# RS232_to_CAN.net
KiCad netlist of a schematic drawn in EAGLE
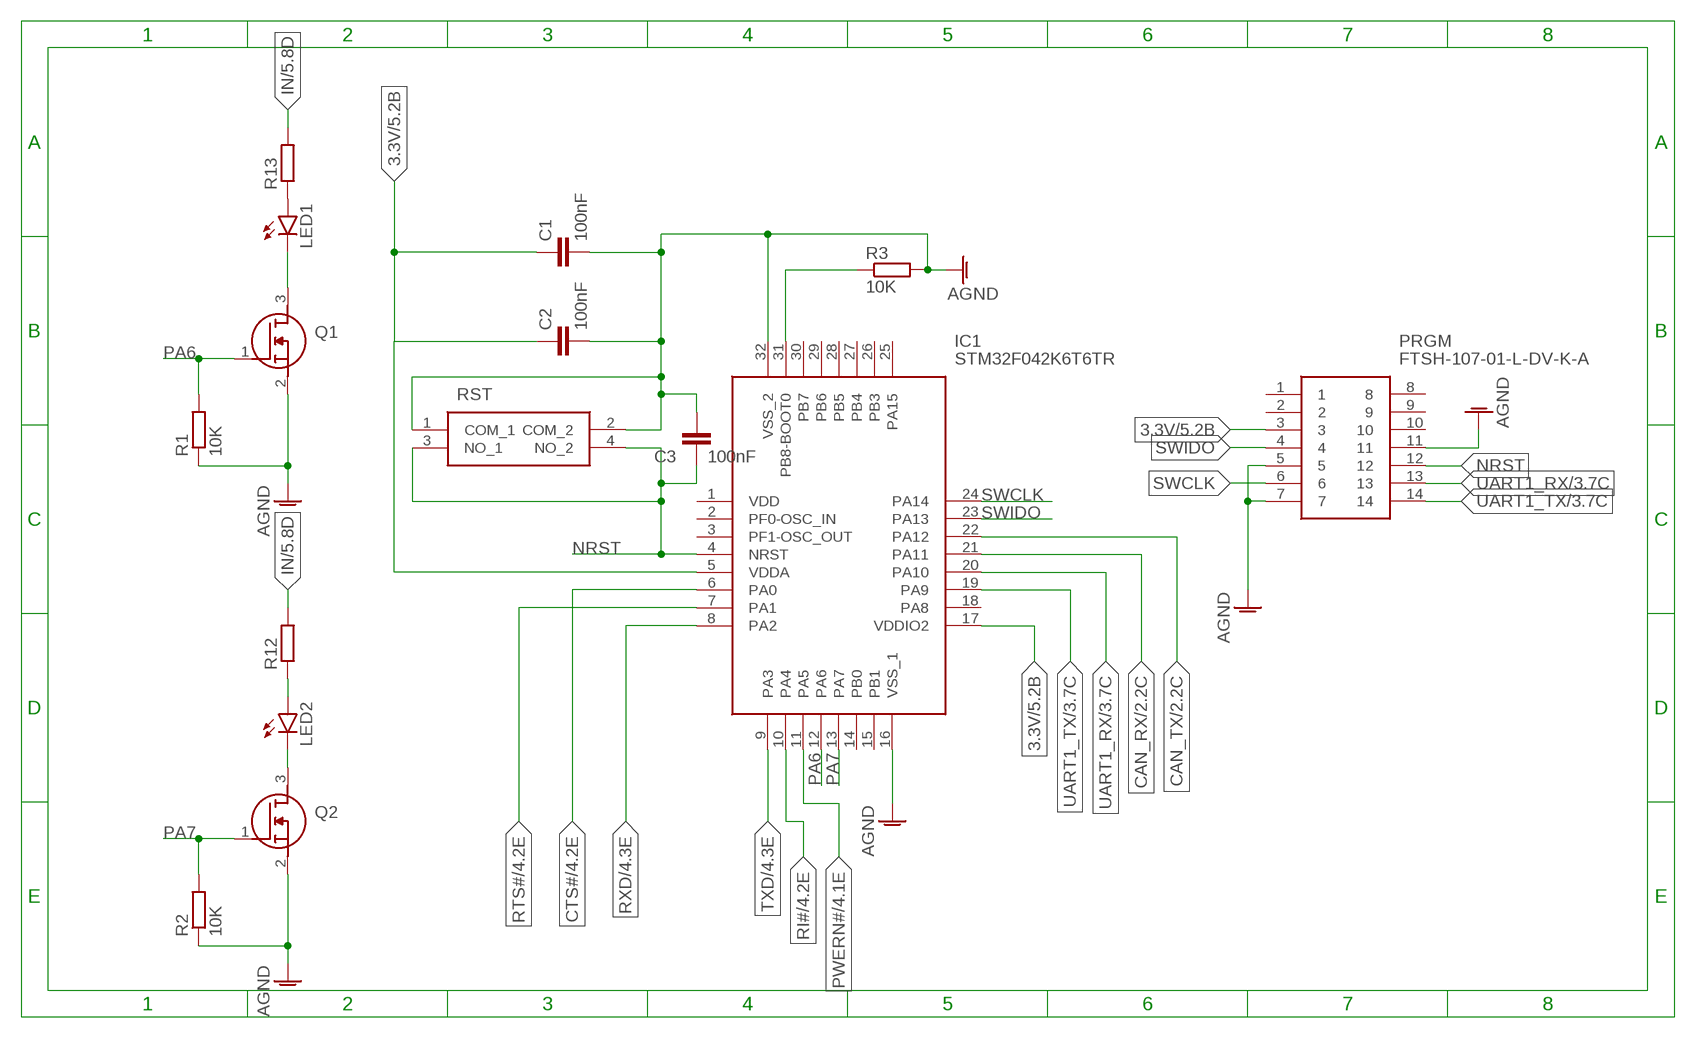
[diagram p0: schematic, sheet 1]
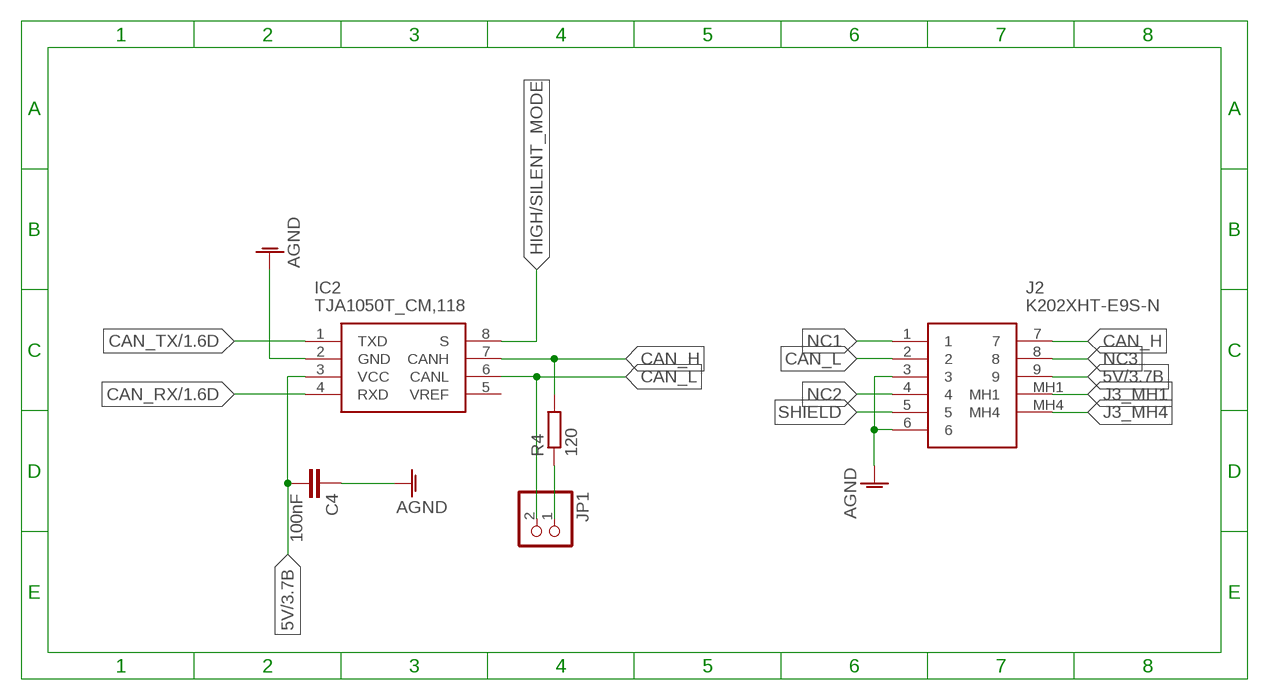
[diagram p1: schematic, sheet 2]
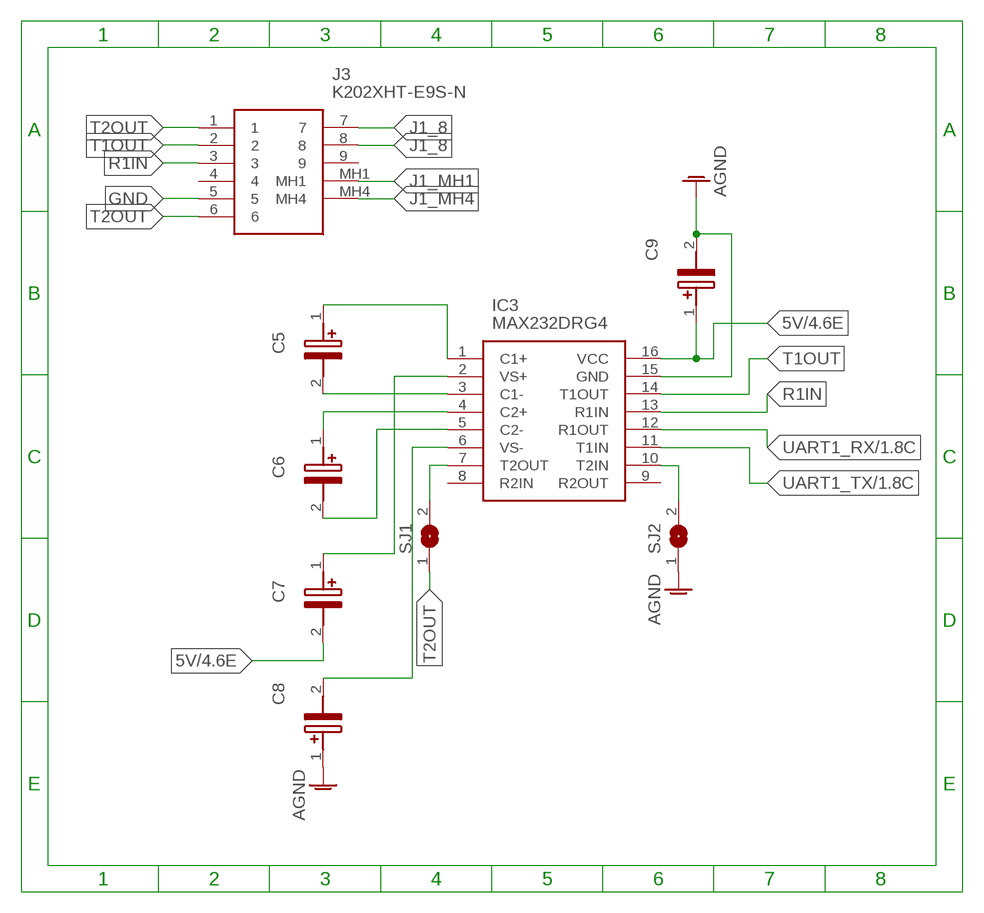
[diagram p2: schematic, sheet 3]
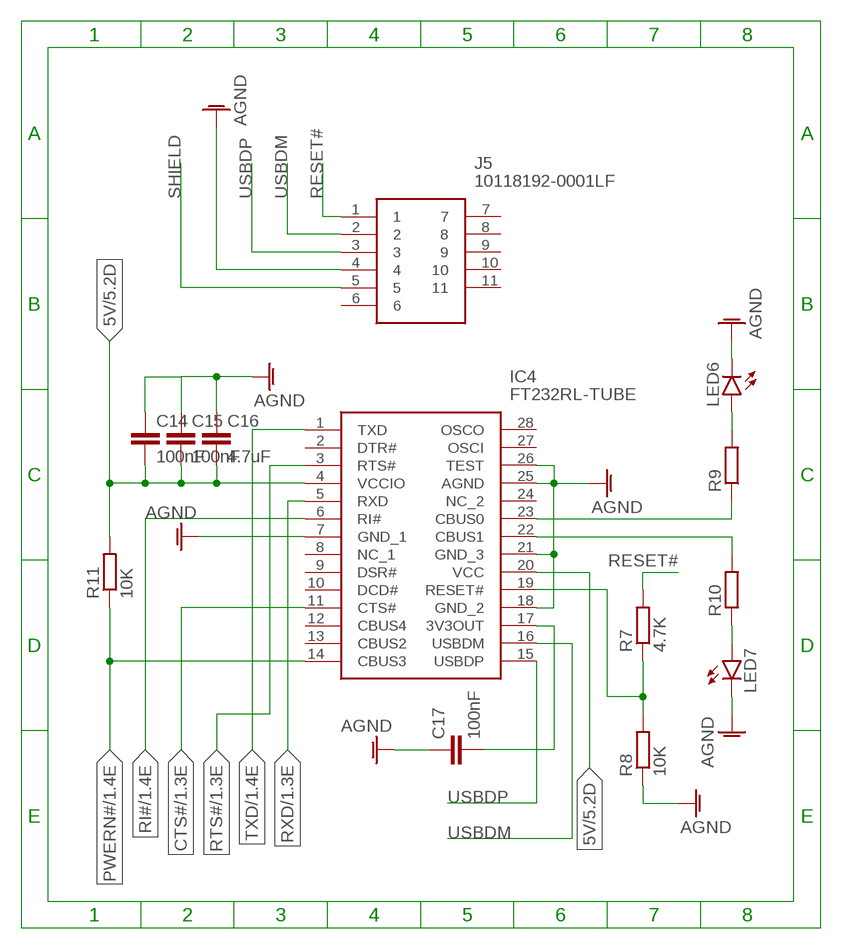
[diagram p3: schematic, sheet 4]
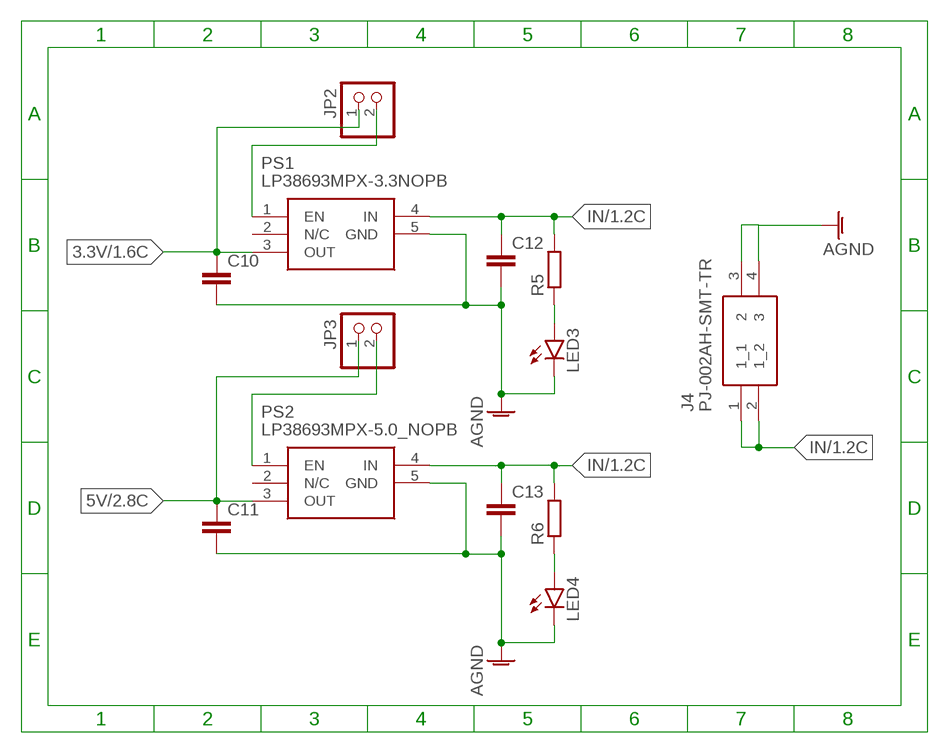
[diagram p4: schematic, sheet 5]

(export (version "E")
  (design (tool "Eeschema 10.0.6"))
  (components
    (comp (ref "C14")
      (value "100nF")
      (footprint "eagle-import:C1206")
      (libsource (lib "eagle-import") (part "C-EU_1206C1206"))
    )
    (comp (ref "C15")
      (value "100nF")
      (footprint "eagle-import:C1206")
      (libsource (lib "eagle-import") (part "C-EU_1206C1206"))
    )
    (comp (ref "C16")
      (value "4.7uF")
      (footprint "eagle-import:C1206")
      (libsource (lib "eagle-import") (part "C-EU_1206C1206"))
    )
    (comp (ref "C17")
      (value "100nF")
      (footprint "eagle-import:C1206")
      (libsource (lib "eagle-import") (part "C-EU_1206C1206"))
    )
    (comp (ref "IC4")
      (value "FT232RL-TUBE")
      (footprint "eagle-import:SOP65P780X200-28N")
      (fields (field (name "MOUSER_PART_NUMBER") "895-FT232RL-TUBE"))
      (libsource (lib "eagle-import") (part "FT232RL-TUBE"))
    )
    (comp (ref "J5")
      (value "10118192-0001LF")
      (footprint "eagle-import:101181920001LF")
      (fields (field (name "MOUSER_PART_NUMBER") "649-10118192-0001LF"))
      (libsource (lib "eagle-import") (part "10118192-0001LF"))
    )
    (comp (ref "LED6")
      (value "LED_1206SMT1206")
      (footprint "eagle-import:1206")
      (libsource (lib "eagle-import") (part "LED_1206SMT1206"))
    )
    (comp (ref "LED7")
      (value "LED_1206SMT1206")
      (footprint "eagle-import:1206")
      (libsource (lib "eagle-import") (part "LED_1206SMT1206"))
    )
    (comp (ref "R7")
      (value "4.7K")
      (footprint "eagle-import:R1206")
      (libsource (lib "eagle-import") (part "R-EU_1206R1206"))
    )
    (comp (ref "R8")
      (value "10K")
      (footprint "eagle-import:R1206")
      (libsource (lib "eagle-import") (part "R-EU_1206R1206"))
    )
    (comp (ref "R9")
      (value "R-EU_1206R1206")
      (footprint "eagle-import:R1206")
      (libsource (lib "eagle-import") (part "R-EU_1206R1206"))
    )
    (comp (ref "R10")
      (value "R-EU_1206R1206")
      (footprint "eagle-import:R1206")
      (libsource (lib "eagle-import") (part "R-EU_1206R1206"))
    )
    (comp (ref "R11")
      (value "10K")
      (footprint "eagle-import:R1206")
      (libsource (lib "eagle-import") (part "R-EU_1206R1206"))
    )
    (comp (ref "C5")
      (value "UWX1H010MCL2GB")
      (footprint "eagle-import:CAPAE430X550N")
      (fields (field (name "MOUSER_PART_NUMBER") "647-UWX1H010MCL2"))
      (libsource (lib "eagle-import") (part "UWX1H010MCL2GB"))
    )
    (comp (ref "C6")
      (value "UWX1H010MCL2GB")
      (footprint "eagle-import:CAPAE430X550N")
      (fields (field (name "MOUSER_PART_NUMBER") "647-UWX1H010MCL2"))
      (libsource (lib "eagle-import") (part "UWX1H010MCL2GB"))
    )
    (comp (ref "C7")
      (value "UWX1H010MCL2GB")
      (footprint "eagle-import:CAPAE430X550N")
      (fields (field (name "MOUSER_PART_NUMBER") "647-UWX1H010MCL2"))
      (libsource (lib "eagle-import") (part "UWX1H010MCL2GB"))
    )
    (comp (ref "C8")
      (value "UWX1H010MCL2GB")
      (footprint "eagle-import:CAPAE430X550N")
      (fields (field (name "MOUSER_PART_NUMBER") "647-UWX1H010MCL2"))
      (libsource (lib "eagle-import") (part "UWX1H010MCL2GB"))
    )
    (comp (ref "C9")
      (value "UWX1H010MCL2GB")
      (footprint "eagle-import:CAPAE430X550N")
      (fields (field (name "MOUSER_PART_NUMBER") "647-UWX1H010MCL2"))
      (libsource (lib "eagle-import") (part "UWX1H010MCL2GB"))
    )
    (comp (ref "IC3")
      (value "MAX232DRG4")
      (footprint "eagle-import:SOIC127P600X175-16N")
      (fields (field (name "MOUSER_PART_NUMBER") "595-MAX232DRG4"))
      (libsource (lib "eagle-import") (part "MAX232DRG4"))
    )
    (comp (ref "J3")
      (value "K202XHT-E9S-N")
      (footprint "eagle-import:K202XHTE9SN")
      (fields (field (name "MOUSER_PART_NUMBER") "806-K202XHT-E9S-N"))
      (libsource (lib "eagle-import") (part "K202XHT-E9S-N"))
    )
    (comp (ref "SJ1") (value "SJ") (footprint "eagle-import:SJ") (libsource (lib "eagle-import") (part "SJ")))
    (comp (ref "SJ2") (value "SJ") (footprint "eagle-import:SJ") (libsource (lib "eagle-import") (part "SJ")))
    (comp (ref "C4")
      (value "100nF")
      (footprint "eagle-import:C1206")
      (libsource (lib "eagle-import") (part "C-EU_1206C1206"))
    )
    (comp (ref "IC2")
      (value "TJA1050T_CM,118")
      (footprint "eagle-import:SOIC127P600X175-8N")
      (fields
        (field (name "MANUFACTURER_PART_NUMBER") "TJA1050T/CM,118")
        (field (name "MOUSER_PART_NUMBER") "771-TJA1050T/CM118")
      )
      (libsource (lib "eagle-import") (part "TJA1050T_CM,118"))
    )
    (comp (ref "J2")
      (value "K202XHT-E9S-N")
      (footprint "eagle-import:K202XHTE9SN")
      (fields (field (name "MOUSER_PART_NUMBER") "806-K202XHT-E9S-N"))
      (libsource (lib "eagle-import") (part "K202XHT-E9S-N"))
    )
    (comp (ref "JP1")
      (value "PINHEADER-1X2")
      (footprint "eagle-import:1X02")
      (libsource (lib "eagle-import") (part "PINHEADER-1X2"))
    )
    (comp (ref "R4")
      (value "120")
      (footprint "eagle-import:R1206")
      (libsource (lib "eagle-import") (part "R-EU_1206R1206"))
    )
    (comp (ref "C10")
      (value "C-EU_805C0805")
      (footprint "eagle-import:C0805")
      (libsource (lib "eagle-import") (part "C-EU_805C0805"))
    )
    (comp (ref "C11")
      (value "C-EU_805C0805")
      (footprint "eagle-import:C0805")
      (libsource (lib "eagle-import") (part "C-EU_805C0805"))
    )
    (comp (ref "C12")
      (value "C-EU_805C0805")
      (footprint "eagle-import:C0805")
      (libsource (lib "eagle-import") (part "C-EU_805C0805"))
    )
    (comp (ref "C13")
      (value "C-EU_805C0805")
      (footprint "eagle-import:C0805")
      (libsource (lib "eagle-import") (part "C-EU_805C0805"))
    )
    (comp (ref "J4")
      (value "PJ-002AH-SMT-TR")
      (footprint "eagle-import:PJ-002AH-SMT-TR")
      (fields (field (name "MOUSER_PART_NUMBER") "490-PJ-002AH-SMT-TR"))
      (libsource (lib "eagle-import") (part "PJ-002AH-SMT-TR"))
    )
    (comp (ref "JP2")
      (value "PINHEADER-1X2")
      (footprint "eagle-import:1X02")
      (libsource (lib "eagle-import") (part "PINHEADER-1X2"))
    )
    (comp (ref "JP3")
      (value "PINHEADER-1X2")
      (footprint "eagle-import:1X02")
      (libsource (lib "eagle-import") (part "PINHEADER-1X2"))
    )
    (comp (ref "LED3")
      (value "LED_1206SMT1206")
      (footprint "eagle-import:1206")
      (libsource (lib "eagle-import") (part "LED_1206SMT1206"))
    )
    (comp (ref "LED4")
      (value "LED_1206SMT1206")
      (footprint "eagle-import:1206")
      (libsource (lib "eagle-import") (part "LED_1206SMT1206"))
    )
    (comp (ref "PS1")
      (value "LP38693MPX-3.3NOPB")
      (footprint "eagle-import:SOT150P700X160-5N")
      (libsource (lib "eagle-import") (part "LP38693MPX-5.0_NOPB"))
    )
    (comp (ref "PS2")
      (value "LP38693MPX-5.0_NOPB")
      (footprint "eagle-import:SOT150P700X160-5N")
      (libsource (lib "eagle-import") (part "LP38693MPX-5.0_NOPB"))
    )
    (comp (ref "R5")
      (value "R-EU_1206R1206")
      (footprint "eagle-import:R1206")
      (libsource (lib "eagle-import") (part "R-EU_1206R1206"))
    )
    (comp (ref "R6")
      (value "R-EU_1206R1206")
      (footprint "eagle-import:R1206")
      (libsource (lib "eagle-import") (part "R-EU_1206R1206"))
    )
    (comp (ref "C1")
      (value "100nF")
      (footprint "eagle-import:C0805")
      (libsource (lib "eagle-import") (part "C-EU_805C0805"))
    )
    (comp (ref "C2")
      (value "100nF")
      (footprint "eagle-import:C0805")
      (libsource (lib "eagle-import") (part "C-EU_805C0805"))
    )
    (comp (ref "C3")
      (value "100nF")
      (footprint "eagle-import:C0805")
      (libsource (lib "eagle-import") (part "C-EU_805C0805"))
    )
    (comp (ref "IC1")
      (value "STM32F042K6T6TR")
      (footprint "eagle-import:QFP80P900X900X160-32N")
      (fields (field (name "MOUSER_PART_NUMBER") "511-STM32F042K6T6TR"))
      (libsource (lib "eagle-import") (part "STM32F042K6T6TR"))
    )
    (comp (ref "LED1")
      (value "LED_1206SMT1206")
      (footprint "eagle-import:1206")
      (libsource (lib "eagle-import") (part "LED_1206SMT1206"))
    )
    (comp (ref "LED2")
      (value "LED_1206SMT1206")
      (footprint "eagle-import:1206")
      (libsource (lib "eagle-import") (part "LED_1206SMT1206"))
    )
    (comp (ref "PRGM")
      (value "FTSH-107-01-L-DV-K-A")
      (footprint "eagle-import:FTSH10701LDVKA")
      (fields (field (name "MOUSER_PART_NUMBER") "200-FTSH10701LDVKA"))
      (libsource (lib "eagle-import") (part "FTSH-107-01-L-DV-K-A"))
    )
    (comp (ref "Q1")
      (value "FDN5632N-F085")
      (footprint "eagle-import:SOT95P237X122-3N")
      (fields (field (name "MOUSER_PART_NUMBER") "512-FDN5632N-F085"))
      (libsource (lib "eagle-import") (part "FDN5632N-F085"))
    )
    (comp (ref "Q2")
      (value "FDN5632N-F085")
      (footprint "eagle-import:SOT95P237X122-3N")
      (fields (field (name "MOUSER_PART_NUMBER") "512-FDN5632N-F085"))
      (libsource (lib "eagle-import") (part "FDN5632N-F085"))
    )
    (comp (ref "R1")
      (value "10K")
      (footprint "eagle-import:R0805")
      (libsource (lib "eagle-import") (part "R-EU_805R0805"))
    )
    (comp (ref "R2")
      (value "10K")
      (footprint "eagle-import:R0805")
      (libsource (lib "eagle-import") (part "R-EU_805R0805"))
    )
    (comp (ref "R3")
      (value "10K")
      (footprint "eagle-import:R1206")
      (libsource (lib "eagle-import") (part "R-EU_1206R1206"))
    )
    (comp (ref "R12")
      (value "R-EU_805R0805")
      (footprint "eagle-import:R0805")
      (libsource (lib "eagle-import") (part "R-EU_805R0805"))
    )
    (comp (ref "R13")
      (value "R-EU_805R0805")
      (footprint "eagle-import:R0805")
      (libsource (lib "eagle-import") (part "R-EU_805R0805"))
    )
    (comp (ref "RST")
      (value "PTS526_SM15_SMTR2_LFS")
      (footprint "eagle-import:PTS526SM15SMTR2LFS")
      (fields
        (field (name "MANUFACTURER_PART_NUMBER") "PTS526 SM15 SMTR2 LFS")
        (field (name "MOUSER_PART_NUMBER") "611-PTS526SM15SMTR2L")
      )
      (libsource (lib "eagle-import") (part "PTS526_SM15_SMTR2_LFS"))
    )
  )
  (nets
    (net (code "1") (name "3.3V") (class "Default")
      (node (ref "C1") (pin "1") (pinfunction "1_1") (pintype "passive"))
      (node (ref "C10") (pin "1") (pinfunction "1_1") (pintype "passive"))
      (node (ref "C2") (pin "1") (pinfunction "1_1") (pintype "passive"))
      (node (ref "IC1") (pin "17") (pinfunction "VDDIO2_17") (pintype "bidirectional"))
      (node (ref "IC1") (pin "5") (pinfunction "VDDA_5") (pintype "bidirectional"))
      (node (ref "JP2") (pin "1") (pinfunction "1_1") (pintype "passive"))
      (node (ref "PRGM") (pin "3") (pinfunction "3_3") (pintype "bidirectional"))
      (node (ref "PS1") (pin "3") (pinfunction "OUT_3") (pintype "bidirectional"))
    )
    (net (code "2") (name "5V") (class "Default")
      (node (ref "C11") (pin "1") (pinfunction "1_1") (pintype "passive"))
      (node (ref "C14") (pin "2") (pinfunction "2_2") (pintype "passive"))
      (node (ref "C15") (pin "2") (pinfunction "2_2") (pintype "passive"))
      (node (ref "C16") (pin "2") (pinfunction "2_2") (pintype "passive"))
      (node (ref "C4") (pin "2") (pinfunction "2_2") (pintype "passive"))
      (node (ref "C7") (pin "2") (pinfunction "-_2") (pintype "bidirectional"))
      (node (ref "C9") (pin "1") (pinfunction "+_1") (pintype "bidirectional"))
      (node (ref "IC2") (pin "3") (pinfunction "VCC_3") (pintype "bidirectional"))
      (node (ref "IC3") (pin "16") (pinfunction "VCC_16") (pintype "bidirectional"))
      (node (ref "IC4") (pin "20") (pinfunction "VCC_20") (pintype "bidirectional"))
      (node (ref "IC4") (pin "4") (pinfunction "VCCIO_4") (pintype "bidirectional"))
      (node (ref "J2") (pin "9") (pinfunction "9_9") (pintype "bidirectional"))
      (node (ref "JP3") (pin "1") (pinfunction "1_1") (pintype "passive"))
      (node (ref "PS2") (pin "3") (pinfunction "OUT_3") (pintype "bidirectional"))
      (node (ref "R11") (pin "2") (pinfunction "2_2") (pintype "passive"))
    )
    (net (code "3") (name "AGND") (class "Default")
      (node (ref "C1") (pin "2") (pinfunction "2_2") (pintype "passive"))
      (node (ref "C10") (pin "2") (pinfunction "2_2") (pintype "passive"))
      (node (ref "C11") (pin "2") (pinfunction "2_2") (pintype "passive"))
      (node (ref "C12") (pin "2") (pinfunction "2_2") (pintype "passive"))
      (node (ref "C13") (pin "2") (pinfunction "2_2") (pintype "passive"))
      (node (ref "C14") (pin "1") (pinfunction "1_1") (pintype "passive"))
      (node (ref "C15") (pin "1") (pinfunction "1_1") (pintype "passive"))
      (node (ref "C16") (pin "1") (pinfunction "1_1") (pintype "passive"))
      (node (ref "C17") (pin "1") (pinfunction "1_1") (pintype "passive"))
      (node (ref "C2") (pin "2") (pinfunction "2_2") (pintype "passive"))
      (node (ref "C3") (pin "1") (pinfunction "1_1") (pintype "passive"))
      (node (ref "C4") (pin "1") (pinfunction "1_1") (pintype "passive"))
      (node (ref "C8") (pin "1") (pinfunction "+_1") (pintype "bidirectional"))
      (node (ref "C9") (pin "2") (pinfunction "-_2") (pintype "bidirectional"))
      (node (ref "IC1") (pin "16") (pinfunction "VSS_1_16") (pintype "bidirectional"))
      (node (ref "IC1") (pin "32") (pinfunction "VSS_2_32") (pintype "bidirectional"))
      (node (ref "IC2") (pin "2") (pinfunction "GND_2") (pintype "bidirectional"))
      (node (ref "IC3") (pin "15") (pinfunction "GND_15") (pintype "bidirectional"))
      (node (ref "IC4") (pin "18") (pinfunction "GND_2_18") (pintype "bidirectional"))
      (node (ref "IC4") (pin "21") (pinfunction "GND_3_21") (pintype "bidirectional"))
      (node (ref "IC4") (pin "25") (pinfunction "AGND_25") (pintype "bidirectional"))
      (node (ref "IC4") (pin "26") (pinfunction "TEST_26") (pintype "bidirectional"))
      (node (ref "IC4") (pin "7") (pinfunction "GND_1_7") (pintype "bidirectional"))
      (node (ref "J2") (pin "3") (pinfunction "3_3") (pintype "bidirectional"))
      (node (ref "J2") (pin "6") (pinfunction "6_6") (pintype "bidirectional"))
      (node (ref "J4") (pin "3") (pinfunction "2_3") (pintype "bidirectional"))
      (node (ref "J4") (pin "4") (pinfunction "3_4") (pintype "bidirectional"))
      (node (ref "J5") (pin "4") (pinfunction "4_4") (pintype "bidirectional"))
      (node (ref "LED3") (pin "C") (pinfunction "C_C") (pintype "passive"))
      (node (ref "LED4") (pin "C") (pinfunction "C_C") (pintype "passive"))
      (node (ref "LED6") (pin "C") (pinfunction "C_C") (pintype "passive"))
      (node (ref "LED7") (pin "C") (pinfunction "C_C") (pintype "passive"))
      (node (ref "PRGM") (pin "11") (pinfunction "11_11") (pintype "bidirectional"))
      (node (ref "PRGM") (pin "5") (pinfunction "5_5") (pintype "bidirectional"))
      (node (ref "PRGM") (pin "7") (pinfunction "7_7") (pintype "bidirectional"))
      (node (ref "PS1") (pin "5") (pinfunction "GND_5") (pintype "bidirectional"))
      (node (ref "PS2") (pin "5") (pinfunction "GND_5") (pintype "bidirectional"))
      (node (ref "Q1") (pin "2") (pinfunction "S_2") (pintype "bidirectional"))
      (node (ref "Q2") (pin "2") (pinfunction "S_2") (pintype "bidirectional"))
      (node (ref "R1") (pin "1") (pinfunction "1_1") (pintype "passive"))
      (node (ref "R2") (pin "1") (pinfunction "1_1") (pintype "passive"))
      (node (ref "R3") (pin "2") (pinfunction "2_2") (pintype "passive"))
      (node (ref "R8") (pin "1") (pinfunction "1_1") (pintype "passive"))
      (node (ref "RST") (pin "1") (pinfunction "COM_1_1") (pintype "bidirectional"))
      (node (ref "RST") (pin "2") (pinfunction "COM_2_2") (pintype "bidirectional"))
      (node (ref "SJ2") (pin "1") (pinfunction "1_1") (pintype "passive"))
    )
    (net (code "4") (name "CAN_H") (class "Default")
      (node (ref "IC2") (pin "7") (pinfunction "CANH_7") (pintype "bidirectional"))
      (node (ref "J2") (pin "7") (pinfunction "7_7") (pintype "bidirectional"))
      (node (ref "R4") (pin "2") (pinfunction "2_2") (pintype "passive"))
    )
    (net (code "5") (name "CAN_L") (class "Default")
      (node (ref "IC2") (pin "6") (pinfunction "CANL_6") (pintype "bidirectional"))
      (node (ref "J2") (pin "2") (pinfunction "2_2") (pintype "bidirectional"))
      (node (ref "JP1") (pin "2") (pinfunction "2_2") (pintype "passive"))
    )
    (net (code "6") (name "CAN_RX") (class "Default")
      (node (ref "IC1") (pin "21") (pinfunction "PA11_21") (pintype "bidirectional"))
      (node (ref "IC2") (pin "4") (pinfunction "RXD_4") (pintype "bidirectional"))
    )
    (net (code "7") (name "CAN_TX") (class "Default")
      (node (ref "IC1") (pin "22") (pinfunction "PA12_22") (pintype "bidirectional"))
      (node (ref "IC2") (pin "1") (pinfunction "TXD_1") (pintype "bidirectional"))
    )
    (net (code "8") (name "CTS#") (class "Default")
      (node (ref "IC1") (pin "6") (pinfunction "PA0_6") (pintype "bidirectional"))
      (node (ref "IC4") (pin "11") (pinfunction "CTS#_11") (pintype "bidirectional"))
    )
    (net (code "9") (name "GND") (class "Default")
      (node (ref "J3") (pin "5") (pinfunction "5_5") (pintype "bidirectional"))
    )
    (net (code "10") (name "HIGH{slash}SILENT_MODE") (class "Default")
      (node (ref "IC2") (pin "8") (pinfunction "S_8") (pintype "bidirectional"))
    )
    (net (code "11") (name "IN") (class "Default")
      (node (ref "C12") (pin "1") (pinfunction "1_1") (pintype "passive"))
      (node (ref "C13") (pin "1") (pinfunction "1_1") (pintype "passive"))
      (node (ref "J4") (pin "1") (pinfunction "1_1_1") (pintype "bidirectional"))
      (node (ref "J4") (pin "2") (pinfunction "1_2_2") (pintype "bidirectional"))
      (node (ref "LED1") (pin "C") (pinfunction "C_C") (pintype "passive"))
      (node (ref "LED2") (pin "C") (pinfunction "C_C") (pintype "passive"))
      (node (ref "PS1") (pin "4") (pinfunction "IN_4") (pintype "bidirectional"))
      (node (ref "PS2") (pin "4") (pinfunction "IN_4") (pintype "bidirectional"))
      (node (ref "Q1") (pin "3") (pinfunction "D_3") (pintype "bidirectional"))
      (node (ref "Q2") (pin "3") (pinfunction "D_3") (pintype "bidirectional"))
      (node (ref "R5") (pin "2") (pinfunction "2_2") (pintype "passive"))
      (node (ref "R6") (pin "2") (pinfunction "2_2") (pintype "passive"))
    )
    (net (code "12") (name "J1_8") (class "Default")
      (node (ref "J3") (pin "7") (pinfunction "7_7") (pintype "bidirectional"))
      (node (ref "J3") (pin "8") (pinfunction "8_8") (pintype "bidirectional"))
    )
    (net (code "13") (name "J1_MH1") (class "Default")
      (node (ref "J3") (pin "MH1") (pinfunction "MH1_MH1") (pintype "bidirectional"))
    )
    (net (code "14") (name "J1_MH4") (class "Default")
      (node (ref "J3") (pin "MH4") (pinfunction "MH4_MH4") (pintype "bidirectional"))
    )
    (net (code "15") (name "J3_MH1") (class "Default")
      (node (ref "J2") (pin "MH1") (pinfunction "MH1_MH1") (pintype "bidirectional"))
    )
    (net (code "16") (name "J3_MH4") (class "Default")
      (node (ref "J2") (pin "MH4") (pinfunction "MH4_MH4") (pintype "bidirectional"))
    )
    (net (code "17") (name "NC1") (class "Default")
      (node (ref "J2") (pin "1") (pinfunction "1_1") (pintype "bidirectional"))
    )
    (net (code "18") (name "NC2") (class "Default")
      (node (ref "J2") (pin "4") (pinfunction "4_4") (pintype "bidirectional"))
    )
    (net (code "19") (name "NC3") (class "Default")
      (node (ref "J2") (pin "8") (pinfunction "8_8") (pintype "bidirectional"))
    )
    (net (code "20") (name "NRST") (class "Default")
      (node (ref "C3") (pin "2") (pinfunction "2_2") (pintype "passive"))
      (node (ref "IC1") (pin "4") (pinfunction "NRST_4") (pintype "bidirectional"))
      (node (ref "PRGM") (pin "12") (pinfunction "12_12") (pintype "bidirectional"))
      (node (ref "RST") (pin "3") (pinfunction "NO_1_3") (pintype "bidirectional"))
      (node (ref "RST") (pin "4") (pinfunction "NO_2_4") (pintype "bidirectional"))
    )
    (net (code "21") (name "Net-(C5-+)") (class "Default")
      (node (ref "C5") (pin "1") (pinfunction "+_1") (pintype "bidirectional"))
      (node (ref "IC3") (pin "1") (pinfunction "C1+_1") (pintype "bidirectional"))
    )
    (net (code "22") (name "Net-(C5--)") (class "Default")
      (node (ref "C5") (pin "2") (pinfunction "-_2") (pintype "bidirectional"))
      (node (ref "IC3") (pin "3") (pinfunction "C1-_3") (pintype "bidirectional"))
    )
    (net (code "23") (name "Net-(C6-+)") (class "Default")
      (node (ref "C6") (pin "1") (pinfunction "+_1") (pintype "bidirectional"))
      (node (ref "IC3") (pin "4") (pinfunction "C2+_4") (pintype "bidirectional"))
    )
    (net (code "24") (name "Net-(C6--)") (class "Default")
      (node (ref "C6") (pin "2") (pinfunction "-_2") (pintype "bidirectional"))
      (node (ref "IC3") (pin "5") (pinfunction "C2-_5") (pintype "bidirectional"))
    )
    (net (code "25") (name "Net-(C7-+)") (class "Default")
      (node (ref "C7") (pin "1") (pinfunction "+_1") (pintype "bidirectional"))
      (node (ref "IC3") (pin "2") (pinfunction "VS+_2") (pintype "bidirectional"))
    )
    (net (code "26") (name "Net-(C8--)") (class "Default")
      (node (ref "C8") (pin "2") (pinfunction "-_2") (pintype "bidirectional"))
      (node (ref "IC3") (pin "6") (pinfunction "VS-_6") (pintype "bidirectional"))
    )
    (net (code "27") (name "Net-(IC1-PB8-BOOT0)") (class "Default")
      (node (ref "IC1") (pin "31") (pinfunction "PB8-BOOT0_31") (pintype "bidirectional"))
      (node (ref "R3") (pin "1") (pinfunction "1_1") (pintype "passive"))
    )
    (net (code "28") (name "Net-(IC3-T2IN)") (class "Default")
      (node (ref "IC3") (pin "10") (pinfunction "T2IN_10") (pintype "bidirectional"))
      (node (ref "SJ2") (pin "2") (pinfunction "2_2") (pintype "passive"))
    )
    (net (code "29") (name "Net-(IC4-3V3OUT)") (class "Default")
      (node (ref "C17") (pin "2") (pinfunction "2_2") (pintype "passive"))
      (node (ref "IC4") (pin "17") (pinfunction "3V3OUT_17") (pintype "bidirectional"))
    )
    (net (code "30") (name "Net-(IC4-CBUS0)") (class "Default")
      (node (ref "IC4") (pin "23") (pinfunction "CBUS0_23") (pintype "bidirectional"))
      (node (ref "R9") (pin "1") (pinfunction "1_1") (pintype "passive"))
    )
    (net (code "31") (name "Net-(IC4-CBUS1)") (class "Default")
      (node (ref "IC4") (pin "22") (pinfunction "CBUS1_22") (pintype "bidirectional"))
      (node (ref "R10") (pin "2") (pinfunction "2_2") (pintype "passive"))
    )
    (net (code "32") (name "Net-(IC4-RESET#)") (class "Default")
      (node (ref "IC4") (pin "19") (pinfunction "RESET#_19") (pintype "bidirectional"))
      (node (ref "R7") (pin "1") (pinfunction "1_1") (pintype "passive"))
      (node (ref "R8") (pin "2") (pinfunction "2_2") (pintype "passive"))
    )
    (net (code "33") (name "Net-(JP1-Pad1)") (class "Default")
      (node (ref "JP1") (pin "1") (pinfunction "1_1") (pintype "passive"))
      (node (ref "R4") (pin "1") (pinfunction "1_1") (pintype "passive"))
    )
    (net (code "34") (name "Net-(LED1-PadA)") (class "Default")
      (node (ref "LED1") (pin "A") (pinfunction "A_A") (pintype "passive"))
      (node (ref "R13") (pin "1") (pinfunction "1_1") (pintype "passive"))
    )
    (net (code "35") (name "Net-(LED2-PadA)") (class "Default")
      (node (ref "LED2") (pin "A") (pinfunction "A_A") (pintype "passive"))
      (node (ref "R12") (pin "1") (pinfunction "1_1") (pintype "passive"))
    )
    (net (code "36") (name "Net-(LED3-PadA)") (class "Default")
      (node (ref "LED3") (pin "A") (pinfunction "A_A") (pintype "passive"))
      (node (ref "R5") (pin "1") (pinfunction "1_1") (pintype "passive"))
    )
    (net (code "37") (name "Net-(LED4-PadA)") (class "Default")
      (node (ref "LED4") (pin "A") (pinfunction "A_A") (pintype "passive"))
      (node (ref "R6") (pin "1") (pinfunction "1_1") (pintype "passive"))
    )
    (net (code "38") (name "Net-(LED6-PadA)") (class "Default")
      (node (ref "LED6") (pin "A") (pinfunction "A_A") (pintype "passive"))
      (node (ref "R9") (pin "2") (pinfunction "2_2") (pintype "passive"))
    )
    (net (code "39") (name "Net-(LED7-PadA)") (class "Default")
      (node (ref "LED7") (pin "A") (pinfunction "A_A") (pintype "passive"))
      (node (ref "R10") (pin "1") (pinfunction "1_1") (pintype "passive"))
    )
    (net (code "40") (name "Net-(PS1-EN)") (class "Default")
      (node (ref "JP2") (pin "2") (pinfunction "2_2") (pintype "passive"))
      (node (ref "PS1") (pin "1") (pinfunction "EN_1") (pintype "bidirectional"))
    )
    (net (code "41") (name "Net-(PS2-EN)") (class "Default")
      (node (ref "JP3") (pin "2") (pinfunction "2_2") (pintype "passive"))
      (node (ref "PS2") (pin "1") (pinfunction "EN_1") (pintype "bidirectional"))
    )
    (net (code "42") (name "PA6") (class "Default")
      (node (ref "IC1") (pin "12") (pinfunction "PA6_12") (pintype "bidirectional"))
      (node (ref "Q1") (pin "1") (pinfunction "G_1") (pintype "bidirectional"))
      (node (ref "R1") (pin "2") (pinfunction "2_2") (pintype "passive"))
    )
    (net (code "43") (name "PA7") (class "Default")
      (node (ref "IC1") (pin "13") (pinfunction "PA7_13") (pintype "bidirectional"))
      (node (ref "Q2") (pin "1") (pinfunction "G_1") (pintype "bidirectional"))
      (node (ref "R2") (pin "2") (pinfunction "2_2") (pintype "passive"))
    )
    (net (code "44") (name "PWERN#") (class "Default")
      (node (ref "IC1") (pin "11") (pinfunction "PA5_11") (pintype "bidirectional"))
      (node (ref "IC4") (pin "14") (pinfunction "CBUS3_14") (pintype "bidirectional"))
      (node (ref "R11") (pin "1") (pinfunction "1_1") (pintype "passive"))
    )
    (net (code "45") (name "R1IN") (class "Default")
      (node (ref "IC3") (pin "13") (pinfunction "R1IN_13") (pintype "bidirectional"))
      (node (ref "J3") (pin "3") (pinfunction "3_3") (pintype "bidirectional"))
    )
    (net (code "46") (name "RESET#") (class "Default")
      (node (ref "J5") (pin "1") (pinfunction "1_1") (pintype "bidirectional"))
      (node (ref "R7") (pin "2") (pinfunction "2_2") (pintype "passive"))
    )
    (net (code "47") (name "RI#") (class "Default")
      (node (ref "IC1") (pin "10") (pinfunction "PA4_10") (pintype "bidirectional"))
      (node (ref "IC4") (pin "6") (pinfunction "RI#_6") (pintype "bidirectional"))
    )
    (net (code "48") (name "RTS#") (class "Default")
      (node (ref "IC1") (pin "7") (pinfunction "PA1_7") (pintype "bidirectional"))
      (node (ref "IC4") (pin "3") (pinfunction "RTS#_3") (pintype "bidirectional"))
    )
    (net (code "49") (name "RXD") (class "Default")
      (node (ref "IC1") (pin "8") (pinfunction "PA2_8") (pintype "bidirectional"))
      (node (ref "IC4") (pin "5") (pinfunction "RXD_5") (pintype "bidirectional"))
    )
    (net (code "50") (name "SHIELD") (class "Default")
      (node (ref "J2") (pin "5") (pinfunction "5_5") (pintype "bidirectional"))
      (node (ref "J5") (pin "5") (pinfunction "5_5") (pintype "bidirectional"))
    )
    (net (code "51") (name "SWCLK") (class "Default")
      (node (ref "IC1") (pin "24") (pinfunction "PA14_24") (pintype "bidirectional"))
      (node (ref "PRGM") (pin "6") (pinfunction "6_6") (pintype "bidirectional"))
    )
    (net (code "52") (name "SWIDO") (class "Default")
      (node (ref "IC1") (pin "23") (pinfunction "PA13_23") (pintype "bidirectional"))
      (node (ref "PRGM") (pin "4") (pinfunction "4_4") (pintype "bidirectional"))
    )
    (net (code "53") (name "T1OUT") (class "Default")
      (node (ref "IC3") (pin "14") (pinfunction "T1OUT_14") (pintype "bidirectional"))
      (node (ref "J3") (pin "2") (pinfunction "2_2") (pintype "bidirectional"))
    )
    (net (code "54") (name "T2OUT") (class "Default")
      (node (ref "IC3") (pin "7") (pinfunction "T2OUT_7") (pintype "bidirectional"))
      (node (ref "J3") (pin "1") (pinfunction "1_1") (pintype "bidirectional"))
      (node (ref "J3") (pin "6") (pinfunction "6_6") (pintype "bidirectional"))
      (node (ref "SJ1") (pin "1") (pinfunction "1_1") (pintype "passive"))
      (node (ref "SJ1") (pin "2") (pinfunction "2_2") (pintype "passive"))
    )
    (net (code "55") (name "TXD") (class "Default")
      (node (ref "IC1") (pin "9") (pinfunction "PA3_9") (pintype "bidirectional"))
      (node (ref "IC4") (pin "1") (pinfunction "TXD_1") (pintype "bidirectional"))
    )
    (net (code "56") (name "UART1_RX") (class "Default")
      (node (ref "IC1") (pin "20") (pinfunction "PA10_20") (pintype "bidirectional"))
      (node (ref "IC3") (pin "12") (pinfunction "R1OUT_12") (pintype "bidirectional"))
      (node (ref "PRGM") (pin "13") (pinfunction "13_13") (pintype "bidirectional"))
    )
    (net (code "57") (name "UART1_TX") (class "Default")
      (node (ref "IC1") (pin "19") (pinfunction "PA9_19") (pintype "bidirectional"))
      (node (ref "IC3") (pin "11") (pinfunction "T1IN_11") (pintype "bidirectional"))
      (node (ref "PRGM") (pin "14") (pinfunction "14_14") (pintype "bidirectional"))
    )
    (net (code "58") (name "USBDM") (class "Default")
      (node (ref "IC4") (pin "16") (pinfunction "USBDM_16") (pintype "bidirectional"))
      (node (ref "J5") (pin "2") (pinfunction "2_2") (pintype "bidirectional"))
    )
    (net (code "59") (name "USBDP") (class "Default")
      (node (ref "IC4") (pin "15") (pinfunction "USBDP_15") (pintype "bidirectional"))
      (node (ref "J5") (pin "3") (pinfunction "3_3") (pintype "bidirectional"))
    )
    (net (code "60") (name "unconnected-(IC1-PA8-Pad18)") (class "Default")
      (node (ref "IC1") (pin "18") (pinfunction "PA8_18") (pintype "bidirectional"))
    )
    (net (code "61") (name "unconnected-(IC1-PA15-Pad25)") (class "Default")
      (node (ref "IC1") (pin "25") (pinfunction "PA15_25") (pintype "bidirectional"))
    )
    (net (code "62") (name "unconnected-(IC1-PB0-Pad14)") (class "Default")
      (node (ref "IC1") (pin "14") (pinfunction "PB0_14") (pintype "bidirectional"))
    )
    (net (code "63") (name "unconnected-(IC1-PB1-Pad15)") (class "Default")
      (node (ref "IC1") (pin "15") (pinfunction "PB1_15") (pintype "bidirectional"))
    )
    (net (code "64") (name "unconnected-(IC1-PB3-Pad26)") (class "Default")
      (node (ref "IC1") (pin "26") (pinfunction "PB3_26") (pintype "bidirectional"))
    )
    (net (code "65") (name "unconnected-(IC1-PB4-Pad27)") (class "Default")
      (node (ref "IC1") (pin "27") (pinfunction "PB4_27") (pintype "bidirectional"))
    )
    (net (code "66") (name "unconnected-(IC1-PB5-Pad28)") (class "Default")
      (node (ref "IC1") (pin "28") (pinfunction "PB5_28") (pintype "bidirectional"))
    )
    (net (code "67") (name "unconnected-(IC1-PB6-Pad29)") (class "Default")
      (node (ref "IC1") (pin "29") (pinfunction "PB6_29") (pintype "bidirectional"))
    )
    (net (code "68") (name "unconnected-(IC1-PB7-Pad30)") (class "Default")
      (node (ref "IC1") (pin "30") (pinfunction "PB7_30") (pintype "bidirectional"))
    )
    (net (code "69") (name "unconnected-(IC1-PF0-OSC_IN-Pad2)") (class "Default")
      (node (ref "IC1") (pin "2") (pinfunction "PF0-OSC_IN_2") (pintype "bidirectional"))
    )
    (net (code "70") (name "unconnected-(IC1-PF1-OSC_OUT-Pad3)") (class "Default")
      (node (ref "IC1") (pin "3") (pinfunction "PF1-OSC_OUT_3") (pintype "bidirectional"))
    )
    (net (code "71") (name "unconnected-(IC1-VDD-Pad1)") (class "Default")
      (node (ref "IC1") (pin "1") (pinfunction "VDD_1") (pintype "bidirectional"))
    )
    (net (code "72") (name "unconnected-(IC2-VREF-Pad5)") (class "Default")
      (node (ref "IC2") (pin "5") (pinfunction "VREF_5") (pintype "bidirectional"))
    )
    (net (code "73") (name "unconnected-(IC3-R2IN-Pad8)") (class "Default")
      (node (ref "IC3") (pin "8") (pinfunction "R2IN_8") (pintype "bidirectional"))
    )
    (net (code "74") (name "unconnected-(IC3-R2OUT-Pad9)") (class "Default")
      (node (ref "IC3") (pin "9") (pinfunction "R2OUT_9") (pintype "bidirectional"))
    )
    (net (code "75") (name "unconnected-(IC4-CBUS2-Pad13)") (class "Default")
      (node (ref "IC4") (pin "13") (pinfunction "CBUS2_13") (pintype "bidirectional"))
    )
    (net (code "76") (name "unconnected-(IC4-CBUS4-Pad12)") (class "Default")
      (node (ref "IC4") (pin "12") (pinfunction "CBUS4_12") (pintype "bidirectional"))
    )
    (net (code "77") (name "unconnected-(IC4-DCD#-Pad10)") (class "Default")
      (node (ref "IC4") (pin "10") (pinfunction "DCD#_10") (pintype "bidirectional"))
    )
    (net (code "78") (name "unconnected-(IC4-DSR#-Pad9)") (class "Default")
      (node (ref "IC4") (pin "9") (pinfunction "DSR#_9") (pintype "bidirectional"))
    )
    (net (code "79") (name "unconnected-(IC4-DTR#-Pad2)") (class "Default")
      (node (ref "IC4") (pin "2") (pinfunction "DTR#_2") (pintype "bidirectional"))
    )
    (net (code "80") (name "unconnected-(IC4-NC_1-Pad8)") (class "Default")
      (node (ref "IC4") (pin "8") (pinfunction "NC_1_8") (pintype "bidirectional"))
    )
    (net (code "81") (name "unconnected-(IC4-NC_2-Pad24)") (class "Default")
      (node (ref "IC4") (pin "24") (pinfunction "NC_2_24") (pintype "bidirectional"))
    )
    (net (code "82") (name "unconnected-(IC4-OSCI-Pad27)") (class "Default")
      (node (ref "IC4") (pin "27") (pinfunction "OSCI_27") (pintype "bidirectional"))
    )
    (net (code "83") (name "unconnected-(IC4-OSCO-Pad28)") (class "Default")
      (node (ref "IC4") (pin "28") (pinfunction "OSCO_28") (pintype "bidirectional"))
    )
    (net (code "84") (name "unconnected-(J3-Pad4)") (class "Default")
      (node (ref "J3") (pin "4") (pinfunction "4_4") (pintype "bidirectional"))
    )
    (net (code "85") (name "unconnected-(J3-Pad9)") (class "Default")
      (node (ref "J3") (pin "9") (pinfunction "9_9") (pintype "bidirectional"))
    )
    (net (code "86") (name "unconnected-(J5-Pad6)") (class "Default")
      (node (ref "J5") (pin "6") (pinfunction "6_6") (pintype "bidirectional"))
    )
    (net (code "87") (name "unconnected-(J5-Pad7)") (class "Default")
      (node (ref "J5") (pin "7") (pinfunction "7_7") (pintype "bidirectional"))
    )
    (net (code "88") (name "unconnected-(J5-Pad8)") (class "Default")
      (node (ref "J5") (pin "8") (pinfunction "8_8") (pintype "bidirectional"))
    )
    (net (code "89") (name "unconnected-(J5-Pad9)") (class "Default")
      (node (ref "J5") (pin "9") (pinfunction "9_9") (pintype "bidirectional"))
    )
    (net (code "90") (name "unconnected-(J5-Pad10)") (class "Default")
      (node (ref "J5") (pin "10") (pinfunction "10_10") (pintype "bidirectional"))
    )
    (net (code "91") (name "unconnected-(J5-Pad11)") (class "Default")
      (node (ref "J5") (pin "11") (pinfunction "11_11") (pintype "bidirectional"))
    )
    (net (code "92") (name "unconnected-(PRGM-Pad1)") (class "Default")
      (node (ref "PRGM") (pin "1") (pinfunction "1_1") (pintype "bidirectional"))
    )
    (net (code "93") (name "unconnected-(PRGM-Pad2)") (class "Default")
      (node (ref "PRGM") (pin "2") (pinfunction "2_2") (pintype "bidirectional"))
    )
    (net (code "94") (name "unconnected-(PRGM-Pad8)") (class "Default")
      (node (ref "PRGM") (pin "8") (pinfunction "8_8") (pintype "bidirectional"))
    )
    (net (code "95") (name "unconnected-(PRGM-Pad9)") (class "Default")
      (node (ref "PRGM") (pin "9") (pinfunction "9_9") (pintype "bidirectional"))
    )
    (net (code "96") (name "unconnected-(PRGM-Pad10)") (class "Default")
      (node (ref "PRGM") (pin "10") (pinfunction "10_10") (pintype "bidirectional"))
    )
    (net (code "97") (name "unconnected-(PS1-N{slash}C-Pad2)") (class "Default")
      (node (ref "PS1") (pin "2") (pinfunction "N/C_2") (pintype "no_connect"))
    )
    (net (code "98") (name "unconnected-(PS2-N{slash}C-Pad2)") (class "Default")
      (node (ref "PS2") (pin "2") (pinfunction "N/C_2") (pintype "no_connect"))
    )
    (net (code "99") (name "unconnected-(R12-Pad2)") (class "Default")
      (node (ref "R12") (pin "2") (pinfunction "2_2") (pintype "passive"))
    )
    (net (code "100") (name "unconnected-(R13-Pad2)") (class "Default")
      (node (ref "R13") (pin "2") (pinfunction "2_2") (pintype "passive"))
    )
  )
)
